# Daughter2.net
KiCad netlist of a schematic drawn in EAGLE
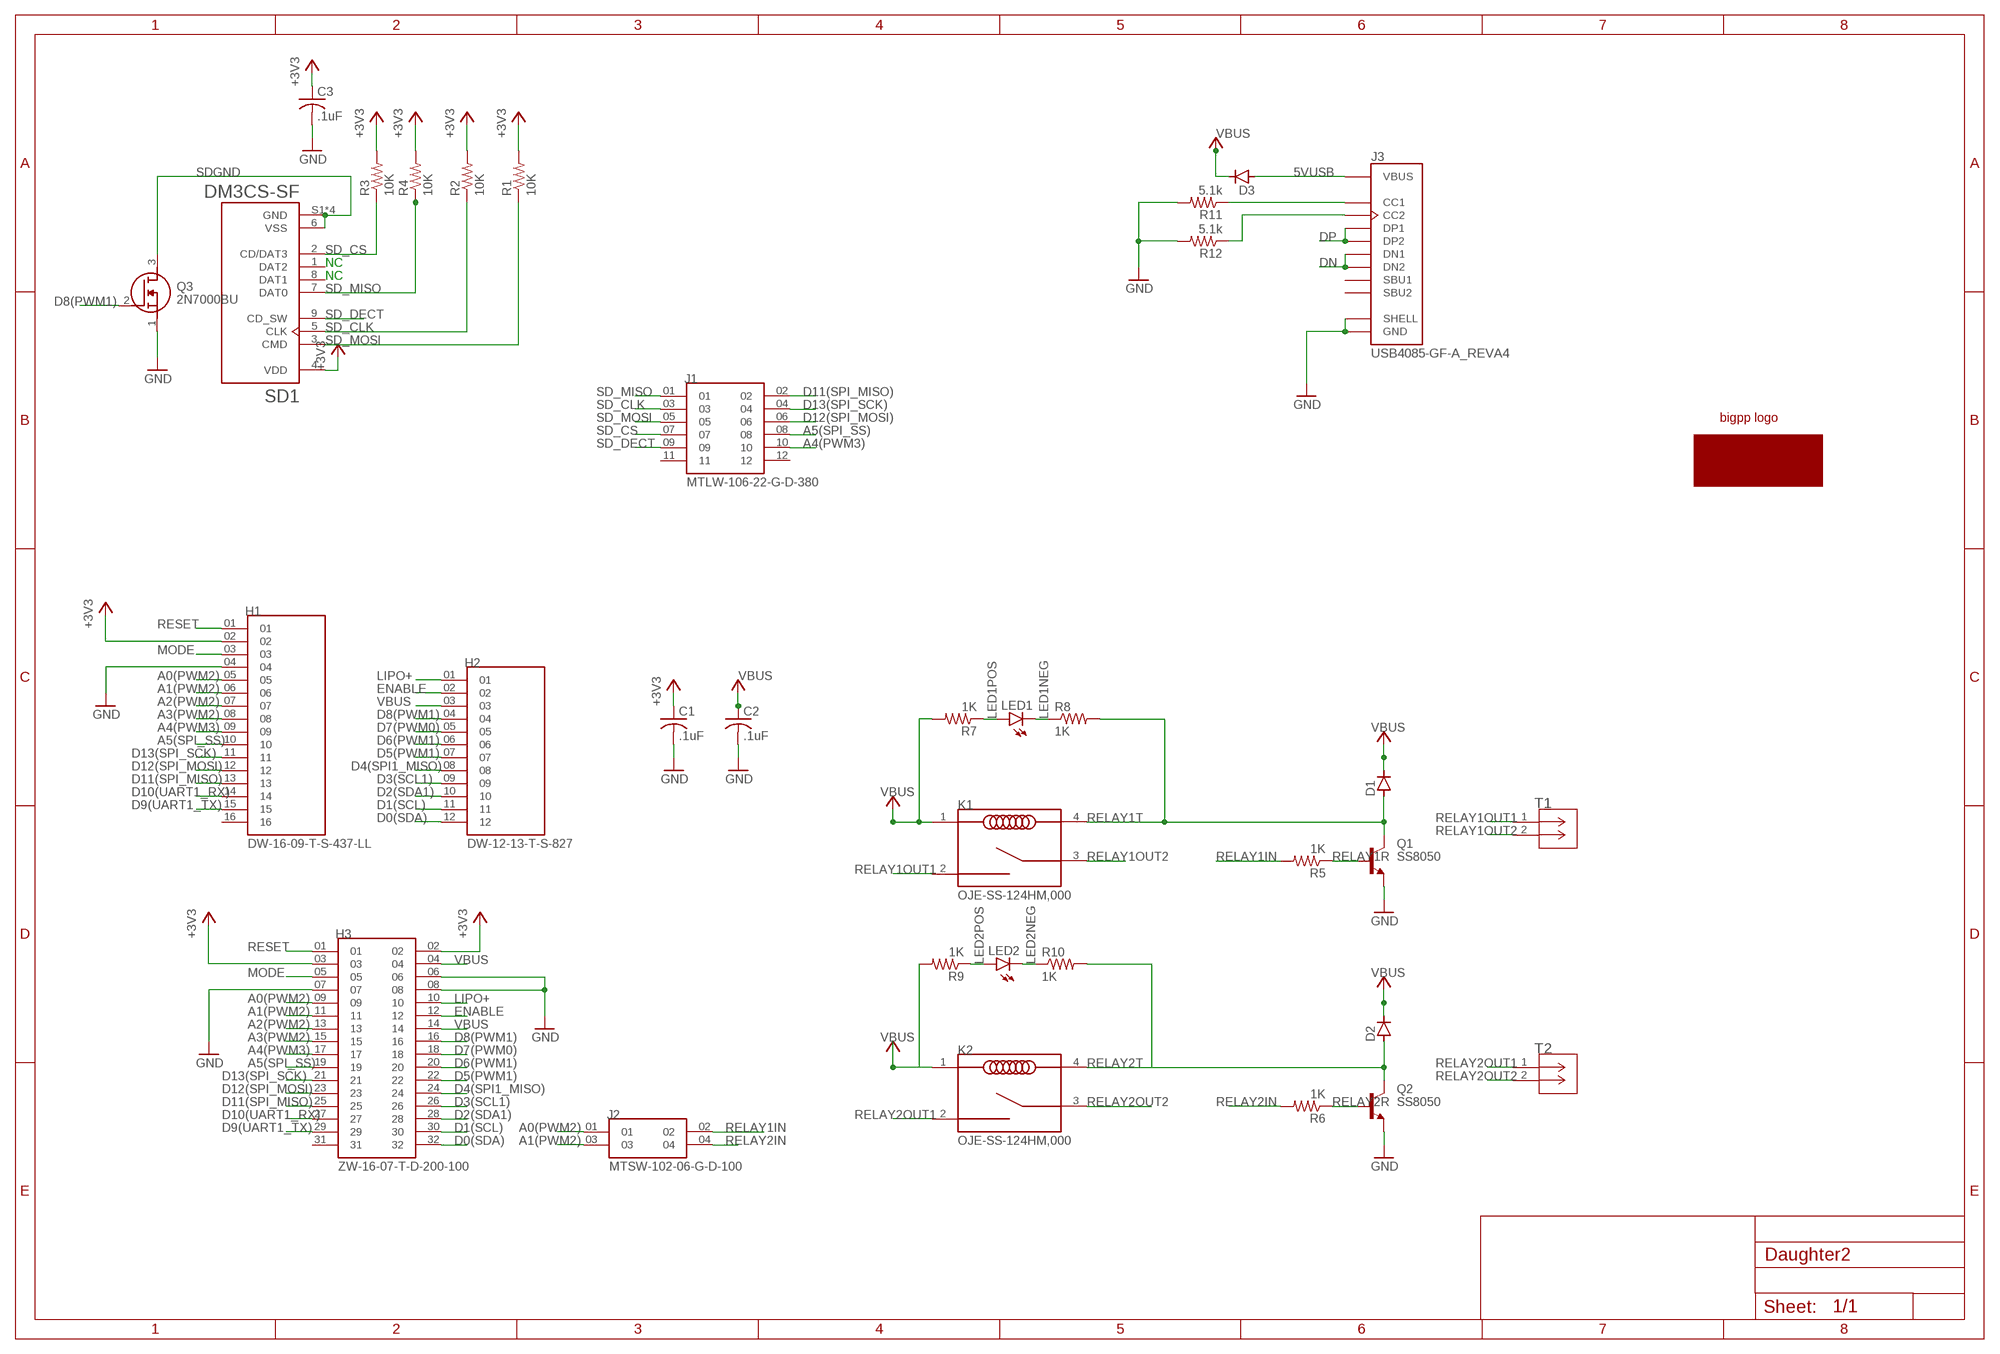
[diagram p0: schematic, sheet 1]

(export (version "E")
  (design (tool "Eeschema 10.0.6"))
  (components
    (comp (ref "C1")
      (value ".1uF")
      (footprint "eagle-import:C0805")
      (libsource (lib "eagle-import") (part "C-USC0805"))
    )
    (comp (ref "C2")
      (value ".1uF")
      (footprint "eagle-import:C0805")
      (libsource (lib "eagle-import") (part "C-USC0805"))
    )
    (comp (ref "C3")
      (value ".1uF")
      (footprint "eagle-import:C0805")
      (libsource (lib "eagle-import") (part "C-USC0805"))
    )
    (comp (ref "D1")
      (value "D-SOD-80")
      (footprint "eagle-import:SOD80")
      (libsource (lib "eagle-import") (part "D-SOD-80"))
    )
    (comp (ref "D2")
      (value "D-SOD-80")
      (footprint "eagle-import:SOD80")
      (libsource (lib "eagle-import") (part "D-SOD-80"))
    )
    (comp (ref "D3")
      (value "D-SOD-80")
      (footprint "eagle-import:SOD80")
      (libsource (lib "eagle-import") (part "D-SOD-80"))
    )
    (comp (ref "H1")
      (value "DW-16-09-T-S-437-LL")
      (footprint "eagle-import:SAMTEC_DW-16-09-T-S-437-LL")
      (fields (field (name "MF") "Samtec"))
      (libsource (lib "eagle-import") (part "DW-16-09-T-S-437-LL"))
    )
    (comp (ref "H2")
      (value "DW-12-13-T-S-827")
      (footprint "eagle-import:SAMTEC_DW-12-13-T-S-827")
      (fields (field (name "MF") "Samtec Inc."))
      (libsource (lib "eagle-import") (part "DW-12-13-T-S-827"))
    )
    (comp (ref "H3")
      (value "ZW-16-07-T-D-200-100")
      (footprint "eagle-import:SAMTEC_ZW-16-07-T-D-200-100")
      (fields (field (name "MF") "Samtec Inc."))
      (libsource (lib "eagle-import") (part "ZW-16-07-T-D-200-100"))
    )
    (comp (ref "J1")
      (value "MTLW-106-22-G-D-380")
      (footprint "eagle-import:SAMTEC_MTLW-106-22-G-D-380")
      (fields (field (name "MF") "Samtec"))
      (libsource (lib "eagle-import") (part "MTLW-106-22-G-D-380"))
    )
    (comp (ref "J2")
      (value "MTSW-102-06-G-D-100")
      (footprint "eagle-import:SAMTEC_MTSW-102-06-G-D-100")
      (fields (field (name "MF") "Samtec Inc."))
      (libsource (lib "eagle-import") (part "MTSW-102-06-G-D-100"))
    )
    (comp (ref "J3")
      (value "USB4085-GF-A_REVA4")
      (footprint "eagle-import:GCT_USB4085-GF-A_REVA4")
      (fields (field (name "MF") "Global Connector Technology") (field (name "MP") "USB4085-GF-A"))
      (libsource (lib "eagle-import") (part "USB4085-GF-A_REVA4"))
    )
    (comp (ref "K1")
      (value "OJE-SS-124HM,000")
      (footprint "eagle-import:RELAY_OJE-SS-124HM,000")
      (fields (field (name "COMMENT") "6-1419128-4") (field (name "MF") "TE Connectivity"))
      (libsource (lib "eagle-import") (part "OJE-SS-124HM,000"))
    )
    (comp (ref "K2")
      (value "OJE-SS-124HM,000")
      (footprint "eagle-import:RELAY_OJE-SS-124HM,000")
      (fields (field (name "COMMENT") "6-1419128-4") (field (name "MF") "TE Connectivity"))
      (libsource (lib "eagle-import") (part "OJE-SS-124HM,000"))
    )
    (comp (ref "LED1")
      (value "LEDCHIP-LED0603")
      (footprint "eagle-import:CHIP-LED0603")
      (libsource (lib "eagle-import") (part "LEDCHIP-LED0603"))
    )
    (comp (ref "LED2")
      (value "LEDCHIP-LED0603")
      (footprint "eagle-import:CHIP-LED0603")
      (libsource (lib "eagle-import") (part "LEDCHIP-LED0603"))
    )
    (comp (ref "Q1")
      (value "SS8050")
      (footprint "eagle-import:SOT-23_BEC")
      (fields (field (name "MF") "Microdiode Electronics"))
      (libsource (lib "eagle-import") (part "SS8050"))
    )
    (comp (ref "Q2")
      (value "SS8050")
      (footprint "eagle-import:SOT-23_BEC")
      (fields (field (name "MF") "Microdiode Electronics"))
      (libsource (lib "eagle-import") (part "SS8050"))
    )
    (comp (ref "Q3")
      (value "2N7000BU")
      (footprint "eagle-import:2N6027")
      (fields (field (name "MOUSER_PART_NUMBER") "512-2N7000BU"))
      (libsource (lib "eagle-import") (part "2N7000BU"))
    )
    (comp (ref "R1")
      (value "10K")
      (footprint "eagle-import:R0805")
      (libsource (lib "eagle-import") (part "R-US_R0805"))
    )
    (comp (ref "R2")
      (value "10K")
      (footprint "eagle-import:R0805")
      (libsource (lib "eagle-import") (part "R-US_R0805"))
    )
    (comp (ref "R3")
      (value "10K")
      (footprint "eagle-import:R0805")
      (libsource (lib "eagle-import") (part "R-US_R0805"))
    )
    (comp (ref "R4")
      (value "10K")
      (footprint "eagle-import:R0805")
      (libsource (lib "eagle-import") (part "R-US_R0805"))
    )
    (comp (ref "R5")
      (value "1K")
      (footprint "eagle-import:R0805")
      (libsource (lib "eagle-import") (part "R-US_R0805"))
    )
    (comp (ref "R6")
      (value "1K")
      (footprint "eagle-import:R0805")
      (libsource (lib "eagle-import") (part "R-US_R0805"))
    )
    (comp (ref "R7")
      (value "1K")
      (footprint "eagle-import:R0805")
      (libsource (lib "eagle-import") (part "R-US_R0805"))
    )
    (comp (ref "R8")
      (value "1K")
      (footprint "eagle-import:R0805")
      (libsource (lib "eagle-import") (part "R-US_R0805"))
    )
    (comp (ref "R9")
      (value "1K")
      (footprint "eagle-import:R0805")
      (libsource (lib "eagle-import") (part "R-US_R0805"))
    )
    (comp (ref "R10")
      (value "1K")
      (footprint "eagle-import:R0805")
      (libsource (lib "eagle-import") (part "R-US_R0805"))
    )
    (comp (ref "R11")
      (value "5.1k")
      (footprint "eagle-import:R0805")
      (libsource (lib "eagle-import") (part "R-US_R0805"))
    )
    (comp (ref "R12")
      (value "5.1k")
      (footprint "eagle-import:R0805")
      (libsource (lib "eagle-import") (part "R-US_R0805"))
    )
    (comp (ref "SD1")
      (value "DM3CS-SF")
      (footprint "eagle-import:HRS_DM3CS-SF")
      (fields (field (name "MF") "Hirose"))
      (libsource (lib "eagle-import") (part "DM3CS-SF"))
    )
    (comp (ref "T1")
      (value "OSTVN02A150")
      (footprint "eagle-import:CONN_OSTVN02A150_OST")
      (fields (field (name "COPYRIGHT") "Copyright (C) 2022 Ultra Librarian. All rights reserved."))
      (libsource (lib "eagle-import") (part "OSTVN02A150"))
    )
    (comp (ref "T2")
      (value "OSTVN02A150")
      (footprint "eagle-import:CONN_OSTVN02A150_OST")
      (fields (field (name "COPYRIGHT") "Copyright (C) 2022 Ultra Librarian. All rights reserved."))
      (libsource (lib "eagle-import") (part "OSTVN02A150"))
    )
    (comp (ref "U$1")
      (value "BIGPP")
      (footprint "eagle-import:BIGPP")
      (libsource (lib "eagle-import") (part "BIGPP"))
    )
  )
  (nets
    (net (code "1") (name "+3V3") (class "Default")
      (node (ref "C1") (pin "1") (pinfunction "1_1") (pintype "passive"))
      (node (ref "C3") (pin "1") (pinfunction "1_1") (pintype "passive"))
      (node (ref "H1") (pin "02") (pinfunction "02_02") (pintype "passive"))
      (node (ref "H3") (pin "02") (pinfunction "02_02") (pintype "passive"))
      (node (ref "H3") (pin "03") (pinfunction "03_03") (pintype "passive"))
      (node (ref "R1") (pin "2") (pinfunction "2_2") (pintype "passive"))
      (node (ref "R2") (pin "2") (pinfunction "2_2") (pintype "passive"))
      (node (ref "R3") (pin "2") (pinfunction "2_2") (pintype "passive"))
      (node (ref "R4") (pin "2") (pinfunction "2_2") (pintype "passive"))
      (node (ref "SD1") (pin "4") (pinfunction "VDD_4") (pintype "passive"))
    )
    (net (code "2") (name "/5VUSB") (class "Default")
      (node (ref "D3") (pin "2") (pinfunction "A_2") (pintype "passive"))
      (node (ref "J3") (pin "A4") (pinfunction "VBUS_A4") (pintype "power_in"))
      (node (ref "J3") (pin "A9") (pinfunction "VBUS_A9") (pintype "power_in"))
      (node (ref "J3") (pin "B4") (pinfunction "VBUS_B4") (pintype "power_in"))
      (node (ref "J3") (pin "B9") (pinfunction "VBUS_B9") (pintype "power_in"))
    )
    (net (code "3") (name "/A0(PWM2)") (class "Default")
      (node (ref "H1") (pin "05") (pinfunction "05_05") (pintype "passive"))
      (node (ref "H3") (pin "09") (pinfunction "09_09") (pintype "passive"))
      (node (ref "J2") (pin "01") (pinfunction "01_01") (pintype "passive"))
    )
    (net (code "4") (name "/A1(PWM2)") (class "Default")
      (node (ref "H1") (pin "06") (pinfunction "06_06") (pintype "passive"))
      (node (ref "H3") (pin "11") (pinfunction "11_11") (pintype "passive"))
      (node (ref "J2") (pin "03") (pinfunction "03_03") (pintype "passive"))
    )
    (net (code "5") (name "/A2(PWM2)") (class "Default")
      (node (ref "H1") (pin "07") (pinfunction "07_07") (pintype "passive"))
      (node (ref "H3") (pin "13") (pinfunction "13_13") (pintype "passive"))
    )
    (net (code "6") (name "/A3(PWM2)") (class "Default")
      (node (ref "H1") (pin "08") (pinfunction "08_08") (pintype "passive"))
      (node (ref "H3") (pin "15") (pinfunction "15_15") (pintype "passive"))
    )
    (net (code "7") (name "/A4(PWM3)") (class "Default")
      (node (ref "H1") (pin "09") (pinfunction "09_09") (pintype "passive"))
      (node (ref "H3") (pin "17") (pinfunction "17_17") (pintype "passive"))
      (node (ref "J1") (pin "10") (pinfunction "10_10") (pintype "passive"))
    )
    (net (code "8") (name "/A5(SPI_SS)") (class "Default")
      (node (ref "H1") (pin "10") (pinfunction "10_10") (pintype "passive"))
      (node (ref "H3") (pin "19") (pinfunction "19_19") (pintype "passive"))
      (node (ref "J1") (pin "08") (pinfunction "08_08") (pintype "passive"))
    )
    (net (code "9") (name "/D0(SDA)") (class "Default")
      (node (ref "H2") (pin "12") (pinfunction "12_12") (pintype "passive"))
      (node (ref "H3") (pin "32") (pinfunction "32_32") (pintype "passive"))
    )
    (net (code "10") (name "/D1(SCL)") (class "Default")
      (node (ref "H2") (pin "11") (pinfunction "11_11") (pintype "passive"))
      (node (ref "H3") (pin "30") (pinfunction "30_30") (pintype "passive"))
    )
    (net (code "11") (name "/D2(SDA1)") (class "Default")
      (node (ref "H2") (pin "10") (pinfunction "10_10") (pintype "passive"))
      (node (ref "H3") (pin "28") (pinfunction "28_28") (pintype "passive"))
    )
    (net (code "12") (name "/D3(SCL1)") (class "Default")
      (node (ref "H2") (pin "09") (pinfunction "09_09") (pintype "passive"))
      (node (ref "H3") (pin "26") (pinfunction "26_26") (pintype "passive"))
    )
    (net (code "13") (name "/D4(SPI1_MISO)") (class "Default")
      (node (ref "H2") (pin "08") (pinfunction "08_08") (pintype "passive"))
      (node (ref "H3") (pin "24") (pinfunction "24_24") (pintype "passive"))
    )
    (net (code "14") (name "/D5(PWM1)") (class "Default")
      (node (ref "H2") (pin "07") (pinfunction "07_07") (pintype "passive"))
      (node (ref "H3") (pin "22") (pinfunction "22_22") (pintype "passive"))
    )
    (net (code "15") (name "/D6(PWM1)") (class "Default")
      (node (ref "H2") (pin "06") (pinfunction "06_06") (pintype "passive"))
      (node (ref "H3") (pin "20") (pinfunction "20_20") (pintype "passive"))
    )
    (net (code "16") (name "/D7(PWM0)") (class "Default")
      (node (ref "H2") (pin "05") (pinfunction "05_05") (pintype "passive"))
      (node (ref "H3") (pin "18") (pinfunction "18_18") (pintype "passive"))
    )
    (net (code "17") (name "/D8(PWM1)") (class "Default")
      (node (ref "H2") (pin "04") (pinfunction "04_04") (pintype "passive"))
      (node (ref "H3") (pin "16") (pinfunction "16_16") (pintype "passive"))
      (node (ref "Q3") (pin "2") (pinfunction "G_2") (pintype "bidirectional"))
    )
    (net (code "18") (name "/D9(UART1_TX)") (class "Default")
      (node (ref "H1") (pin "15") (pinfunction "15_15") (pintype "passive"))
      (node (ref "H3") (pin "29") (pinfunction "29_29") (pintype "passive"))
    )
    (net (code "19") (name "/D10(UART1_RX)") (class "Default")
      (node (ref "H1") (pin "14") (pinfunction "14_14") (pintype "passive"))
      (node (ref "H3") (pin "27") (pinfunction "27_27") (pintype "passive"))
    )
    (net (code "20") (name "/D11(SPI_MISO)") (class "Default")
      (node (ref "H1") (pin "13") (pinfunction "13_13") (pintype "passive"))
      (node (ref "H3") (pin "25") (pinfunction "25_25") (pintype "passive"))
      (node (ref "J1") (pin "02") (pinfunction "02_02") (pintype "passive"))
    )
    (net (code "21") (name "/D12(SPI_MOSI)") (class "Default")
      (node (ref "H1") (pin "12") (pinfunction "12_12") (pintype "passive"))
      (node (ref "H3") (pin "23") (pinfunction "23_23") (pintype "passive"))
      (node (ref "J1") (pin "06") (pinfunction "06_06") (pintype "passive"))
    )
    (net (code "22") (name "/D13(SPI_SCK)") (class "Default")
      (node (ref "H1") (pin "11") (pinfunction "11_11") (pintype "passive"))
      (node (ref "H3") (pin "21") (pinfunction "21_21") (pintype "passive"))
      (node (ref "J1") (pin "04") (pinfunction "04_04") (pintype "passive"))
    )
    (net (code "23") (name "/DN") (class "Default")
      (node (ref "J3") (pin "A7") (pinfunction "DN1_A7") (pintype "bidirectional"))
      (node (ref "J3") (pin "B7") (pinfunction "DN2_B7") (pintype "bidirectional"))
    )
    (net (code "24") (name "/DP") (class "Default")
      (node (ref "J3") (pin "A6") (pinfunction "DP1_A6") (pintype "bidirectional"))
      (node (ref "J3") (pin "B6") (pinfunction "DP2_B6") (pintype "bidirectional"))
    )
    (net (code "25") (name "/ENABLE") (class "Default")
      (node (ref "H2") (pin "02") (pinfunction "02_02") (pintype "passive"))
      (node (ref "H3") (pin "12") (pinfunction "12_12") (pintype "passive"))
    )
    (net (code "26") (name "/LED1NEG") (class "Default")
      (node (ref "LED1") (pin "C") (pinfunction "C_C") (pintype "passive"))
      (node (ref "R8") (pin "1") (pinfunction "1_1") (pintype "passive"))
    )
    (net (code "27") (name "/LED1POS") (class "Default")
      (node (ref "LED1") (pin "A") (pinfunction "A_A") (pintype "passive"))
      (node (ref "R7") (pin "1") (pinfunction "1_1") (pintype "passive"))
    )
    (net (code "28") (name "/LED2NEG") (class "Default")
      (node (ref "LED2") (pin "C") (pinfunction "C_C") (pintype "passive"))
      (node (ref "R10") (pin "1") (pinfunction "1_1") (pintype "passive"))
    )
    (net (code "29") (name "/LED2POS") (class "Default")
      (node (ref "LED2") (pin "A") (pinfunction "A_A") (pintype "passive"))
      (node (ref "R9") (pin "1") (pinfunction "1_1") (pintype "passive"))
    )
    (net (code "30") (name "/LIPO+") (class "Default")
      (node (ref "H2") (pin "01") (pinfunction "01_01") (pintype "passive"))
      (node (ref "H3") (pin "10") (pinfunction "10_10") (pintype "passive"))
    )
    (net (code "31") (name "/MODE") (class "Default")
      (node (ref "H1") (pin "03") (pinfunction "03_03") (pintype "passive"))
      (node (ref "H3") (pin "05") (pinfunction "05_05") (pintype "passive"))
    )
    (net (code "32") (name "/RELAY1IN") (class "Default")
      (node (ref "J2") (pin "02") (pinfunction "02_02") (pintype "passive"))
      (node (ref "R5") (pin "2") (pinfunction "2_2") (pintype "passive"))
    )
    (net (code "33") (name "/RELAY1OUT1") (class "Default")
      (node (ref "K1") (pin "2") (pinfunction "2_2") (pintype "passive"))
      (node (ref "T1") (pin "1") (pinfunction "1_1") (pintype "passive"))
    )
    (net (code "34") (name "/RELAY1OUT2") (class "Default")
      (node (ref "K1") (pin "3") (pinfunction "3_3") (pintype "passive"))
      (node (ref "T1") (pin "2") (pinfunction "2_2") (pintype "passive"))
    )
    (net (code "35") (name "/RELAY1R") (class "Default")
      (node (ref "Q1") (pin "B") (pinfunction "B_B") (pintype "passive"))
      (node (ref "R5") (pin "1") (pinfunction "1_1") (pintype "passive"))
    )
    (net (code "36") (name "/RELAY1T") (class "Default")
      (node (ref "D1") (pin "2") (pinfunction "A_2") (pintype "passive"))
      (node (ref "K1") (pin "4") (pinfunction "4_4") (pintype "passive"))
      (node (ref "Q1") (pin "C") (pinfunction "C_C") (pintype "passive"))
      (node (ref "R8") (pin "2") (pinfunction "2_2") (pintype "passive"))
    )
    (net (code "37") (name "/RELAY2IN") (class "Default")
      (node (ref "J2") (pin "04") (pinfunction "04_04") (pintype "passive"))
      (node (ref "R6") (pin "2") (pinfunction "2_2") (pintype "passive"))
    )
    (net (code "38") (name "/RELAY2OUT1") (class "Default")
      (node (ref "K2") (pin "2") (pinfunction "2_2") (pintype "passive"))
      (node (ref "T2") (pin "1") (pinfunction "1_1") (pintype "passive"))
    )
    (net (code "39") (name "/RELAY2OUT2") (class "Default")
      (node (ref "K2") (pin "3") (pinfunction "3_3") (pintype "passive"))
      (node (ref "T2") (pin "2") (pinfunction "2_2") (pintype "passive"))
    )
    (net (code "40") (name "/RELAY2R") (class "Default")
      (node (ref "Q2") (pin "B") (pinfunction "B_B") (pintype "passive"))
      (node (ref "R6") (pin "1") (pinfunction "1_1") (pintype "passive"))
    )
    (net (code "41") (name "/RELAY2T") (class "Default")
      (node (ref "D2") (pin "2") (pinfunction "A_2") (pintype "passive"))
      (node (ref "K2") (pin "4") (pinfunction "4_4") (pintype "passive"))
      (node (ref "Q2") (pin "C") (pinfunction "C_C") (pintype "passive"))
    )
    (net (code "42") (name "/RESET") (class "Default")
      (node (ref "H1") (pin "01") (pinfunction "01_01") (pintype "passive"))
      (node (ref "H3") (pin "01") (pinfunction "01_01") (pintype "passive"))
    )
    (net (code "43") (name "/SDGND") (class "Default")
      (node (ref "Q3") (pin "3") (pinfunction "D_3") (pintype "bidirectional"))
      (node (ref "SD1") (pin "6") (pinfunction "VSS_6") (pintype "passive"))
      (node (ref "SD1") (pin "S1") (pinfunction "GND_S1") (pintype "passive"))
      (node (ref "SD1") (pin "S2") (pinfunction "GND_S2") (pintype "passive"))
      (node (ref "SD1") (pin "S3") (pinfunction "GND_S3") (pintype "passive"))
      (node (ref "SD1") (pin "S5") (pinfunction "GND_S5") (pintype "passive"))
    )
    (net (code "44") (name "/SD_CLK") (class "Default")
      (node (ref "J1") (pin "03") (pinfunction "03_03") (pintype "passive"))
      (node (ref "R2") (pin "1") (pinfunction "1_1") (pintype "passive"))
      (node (ref "SD1") (pin "5") (pinfunction "CLK_5") (pintype "passive"))
    )
    (net (code "45") (name "/SD_CS") (class "Default")
      (node (ref "J1") (pin "07") (pinfunction "07_07") (pintype "passive"))
      (node (ref "R3") (pin "1") (pinfunction "1_1") (pintype "passive"))
      (node (ref "SD1") (pin "2") (pinfunction "CD/DAT3_2") (pintype "passive"))
    )
    (net (code "46") (name "/SD_DECT") (class "Default")
      (node (ref "J1") (pin "09") (pinfunction "09_09") (pintype "passive"))
      (node (ref "SD1") (pin "9") (pinfunction "CD_SW_9") (pintype "passive"))
    )
    (net (code "47") (name "/SD_MISO") (class "Default")
      (node (ref "J1") (pin "01") (pinfunction "01_01") (pintype "passive"))
      (node (ref "R4") (pin "1") (pinfunction "1_1") (pintype "passive"))
      (node (ref "SD1") (pin "7") (pinfunction "DAT0_7") (pintype "passive"))
    )
    (net (code "48") (name "/SD_MOSI") (class "Default")
      (node (ref "J1") (pin "05") (pinfunction "05_05") (pintype "passive"))
      (node (ref "R1") (pin "1") (pinfunction "1_1") (pintype "passive"))
      (node (ref "SD1") (pin "3") (pinfunction "CMD_3") (pintype "passive"))
    )
    (net (code "49") (name "GND") (class "Default")
      (node (ref "C1") (pin "2") (pinfunction "2_2") (pintype "passive"))
      (node (ref "C2") (pin "2") (pinfunction "2_2") (pintype "passive"))
      (node (ref "C3") (pin "2") (pinfunction "2_2") (pintype "passive"))
      (node (ref "H1") (pin "04") (pinfunction "04_04") (pintype "passive"))
      (node (ref "H3") (pin "06") (pinfunction "06_06") (pintype "passive"))
      (node (ref "H3") (pin "07") (pinfunction "07_07") (pintype "passive"))
      (node (ref "H3") (pin "08") (pinfunction "08_08") (pintype "passive"))
      (node (ref "J3") (pin "A1") (pinfunction "GND_A1") (pintype "passive"))
      (node (ref "J3") (pin "A12") (pinfunction "GND_A12") (pintype "passive"))
      (node (ref "J3") (pin "B1") (pinfunction "GND_B1") (pintype "passive"))
      (node (ref "J3") (pin "B12") (pinfunction "GND_B12") (pintype "passive"))
      (node (ref "J3") (pin "P1") (pinfunction "SHELL_P1") (pintype "passive"))
      (node (ref "J3") (pin "P2") (pinfunction "SHELL_P2") (pintype "passive"))
      (node (ref "J3") (pin "P3") (pinfunction "SHELL_P3") (pintype "passive"))
      (node (ref "J3") (pin "P4") (pinfunction "SHELL_P4") (pintype "passive"))
      (node (ref "Q1") (pin "E") (pinfunction "E_E") (pintype "passive"))
      (node (ref "Q2") (pin "E") (pinfunction "E_E") (pintype "passive"))
      (node (ref "Q3") (pin "1") (pinfunction "S_1") (pintype "bidirectional"))
      (node (ref "R11") (pin "2") (pinfunction "2_2") (pintype "passive"))
      (node (ref "R12") (pin "2") (pinfunction "2_2") (pintype "passive"))
    )
    (net (code "50") (name "Net-(J3-CC1)") (class "Default")
      (node (ref "J3") (pin "A5") (pinfunction "CC1_A5") (pintype "bidirectional"))
      (node (ref "R11") (pin "1") (pinfunction "1_1") (pintype "passive"))
    )
    (net (code "51") (name "Net-(J3-CC2)") (class "Default")
      (node (ref "J3") (pin "B5") (pinfunction "CC2_B5") (pintype "bidirectional"))
      (node (ref "R12") (pin "1") (pinfunction "1_1") (pintype "passive"))
    )
    (net (code "52") (name "VCC") (class "Default")
      (node (ref "C2") (pin "1") (pinfunction "1_1") (pintype "passive"))
      (node (ref "D1") (pin "1") (pinfunction "C_1") (pintype "passive"))
      (node (ref "D2") (pin "1") (pinfunction "C_1") (pintype "passive"))
      (node (ref "D3") (pin "1") (pinfunction "C_1") (pintype "passive"))
      (node (ref "H2") (pin "03") (pinfunction "03_03") (pintype "passive"))
      (node (ref "H3") (pin "04") (pinfunction "04_04") (pintype "passive"))
      (node (ref "H3") (pin "14") (pinfunction "14_14") (pintype "passive"))
      (node (ref "K1") (pin "1") (pinfunction "1_1") (pintype "passive"))
      (node (ref "K2") (pin "1") (pinfunction "1_1") (pintype "passive"))
      (node (ref "R7") (pin "2") (pinfunction "2_2") (pintype "passive"))
    )
    (net (code "53") (name "unconnected-(H1-Pad16)") (class "Default")
      (node (ref "H1") (pin "16") (pinfunction "16_16") (pintype "passive"))
    )
    (net (code "54") (name "unconnected-(H3-Pad31)") (class "Default")
      (node (ref "H3") (pin "31") (pinfunction "31_31") (pintype "passive"))
    )
    (net (code "55") (name "unconnected-(J1-Pad11)") (class "Default")
      (node (ref "J1") (pin "11") (pinfunction "11_11") (pintype "passive"))
    )
    (net (code "56") (name "unconnected-(J1-Pad12)") (class "Default")
      (node (ref "J1") (pin "12") (pinfunction "12_12") (pintype "passive"))
    )
    (net (code "57") (name "unconnected-(J3-SBU1-PadA8)") (class "Default")
      (node (ref "J3") (pin "A8") (pinfunction "SBU1_A8") (pintype "bidirectional"))
    )
    (net (code "58") (name "unconnected-(J3-SBU2-PadB8)") (class "Default")
      (node (ref "J3") (pin "B8") (pinfunction "SBU2_B8") (pintype "bidirectional"))
    )
    (net (code "59") (name "unconnected-(R9-Pad2)") (class "Default")
      (node (ref "R9") (pin "2") (pinfunction "2_2") (pintype "passive"))
    )
    (net (code "60") (name "unconnected-(R10-Pad2)") (class "Default")
      (node (ref "R10") (pin "2") (pinfunction "2_2") (pintype "passive"))
    )
    (net (code "61") (name "unconnected-(SD1-DAT1-Pad8)") (class "Default")
      (node (ref "SD1") (pin "8") (pinfunction "DAT1_8") (pintype "passive"))
    )
    (net (code "62") (name "unconnected-(SD1-DAT2-Pad1)") (class "Default")
      (node (ref "SD1") (pin "1") (pinfunction "DAT2_1") (pintype "passive"))
    )
  )
)
